# Mircod_TEST_LIST_MAIN.net
KiCad netlist of a schematic drawn in Altium Designer
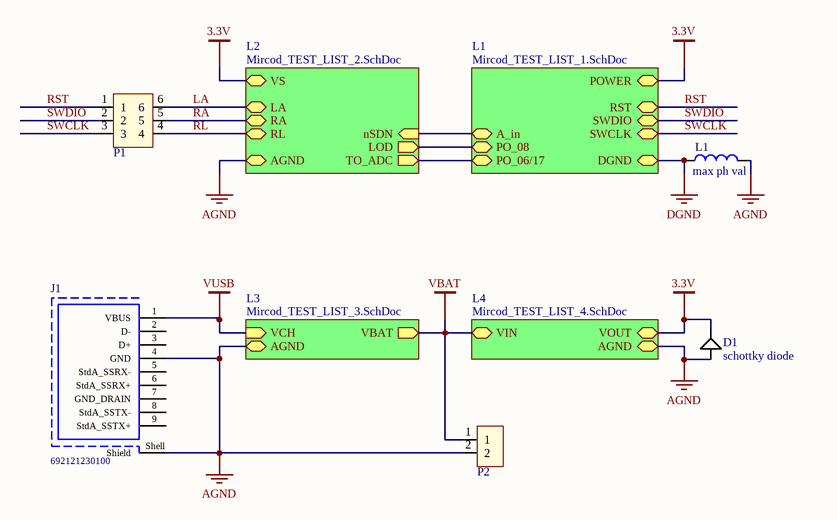
[diagram p0: Mircod_TEST_LIST_MAIN.SchDoc]

(export (version "E")
  (design (tool "Eeschema 10.0.6"))
  (components
    (comp (ref "D1")
      (value "schottky diode")
      (footprint "MIRCOD:DSMD_0603")
      (libsource (lib "MIRCOD") (part "DIODE"))
    )
    (comp (ref "J1")
      (value "692121230100")
      (footprint "692121230100")
      (description "USB 3.0 Type A Receptacle WR-COM, Horizontal, THT, with Clips, with 1.04 mm Offset")
      (fields (field (name "PUBLISHER") "Wurth Elektronik"))
      (libsource (lib "Altium_WR-COM_USB-Connectors (rev19a)") (part "692121230100"))
    )
    (comp (ref "L1")
      (value "max ph val")
      (footprint "MIRCOD:RDSMD_0603")
      (libsource (lib "MIRCOD") (part "INDUCTOR"))
    )
    (comp (ref "P1") (value "PORT") (footprint "MIRCOD:H_3X2_1_27") (libsource (lib "MIRCOD") (part "PORT")))
    (comp (ref "P2")
      (value "Header 1x2")
      (footprint "MIRCOD:header-2")
      (libsource (lib "MIRCOD") (part "Header 1x2"))
    )
  )
  (nets
    (net (code "2") (name "/LA") (class "Default")
      (node (ref "P1") (pin "6") (pinfunction "6_6") (pintype "passive"))
    )
    (net (code "4") (name "/RA") (class "Default")
      (node (ref "P1") (pin "5") (pinfunction "5_5") (pintype "passive"))
    )
    (net (code "5") (name "/RL") (class "Default")
      (node (ref "P1") (pin "4") (pinfunction "4_4") (pintype "passive"))
    )
    (net (code "6") (name "/RST") (class "Default")
      (node (ref "P1") (pin "1") (pinfunction "1_1") (pintype "passive"))
    )
    (net (code "7") (name "/SWCLK") (class "Default")
      (node (ref "P1") (pin "3") (pinfunction "3_3") (pintype "passive"))
    )
    (net (code "8") (name "/SWDIO") (class "Default")
      (node (ref "P1") (pin "2") (pinfunction "2_2") (pintype "passive"))
    )
    (net (code "10") (name "3.3V") (class "Default")
      (node (ref "D1") (pin "2") (pinfunction "2_2") (pintype "passive"))
    )
    (net (code "11") (name "AGND") (class "Default")
      (node (ref "D1") (pin "1") (pinfunction "1_1") (pintype "passive"))
      (node (ref "J1") (pin "4") (pinfunction "GND_4") (pintype "passive"))
      (node (ref "J1") (pin "Shell") (pinfunction "Shield_Shell") (pintype "passive"))
      (node (ref "L1") (pin "1") (pinfunction "1_1") (pintype "passive"))
      (node (ref "P2") (pin "2") (pinfunction "2_2") (pintype "passive"))
    )
    (net (code "12") (name "DGND") (class "Default")
      (node (ref "L1") (pin "2") (pinfunction "2_2") (pintype "passive"))
    )
    (net (code "13") (name "VBAT") (class "Default")
      (node (ref "P2") (pin "1") (pinfunction "1_1") (pintype "passive"))
    )
    (net (code "14") (name "VUSB") (class "Default")
      (node (ref "J1") (pin "1") (pinfunction "VBUS_1") (pintype "passive"))
    )
    (net (code "15") (name "unconnected-(J1-D+-Pad3)") (class "Default")
      (node (ref "J1") (pin "3") (pinfunction "D+_3") (pintype "passive"))
    )
    (net (code "16") (name "unconnected-(J1-D--Pad2)") (class "Default")
      (node (ref "J1") (pin "2") (pinfunction "D-_2") (pintype "passive"))
    )
    (net (code "17") (name "unconnected-(J1-GND_DRAIN-Pad7)") (class "Default")
      (node (ref "J1") (pin "7") (pinfunction "GND_DRAIN_7") (pintype "passive"))
    )
    (net (code "18") (name "unconnected-(J1-StdA_SSRX+-Pad6)") (class "Default")
      (node (ref "J1") (pin "6") (pinfunction "StdA_SSRX+_6") (pintype "passive"))
    )
    (net (code "19") (name "unconnected-(J1-StdA_SSRX--Pad5)") (class "Default")
      (node (ref "J1") (pin "5") (pinfunction "StdA_SSRX-_5") (pintype "passive"))
    )
    (net (code "20") (name "unconnected-(J1-StdA_SSTX+-Pad9)") (class "Default")
      (node (ref "J1") (pin "9") (pinfunction "StdA_SSTX+_9") (pintype "passive"))
    )
    (net (code "21") (name "unconnected-(J1-StdA_SSTX--Pad8)") (class "Default")
      (node (ref "J1") (pin "8") (pinfunction "StdA_SSTX-_8") (pintype "passive"))
    )
  )
)
